# USB.net
KiCad netlist of a schematic drawn in Altium Designer
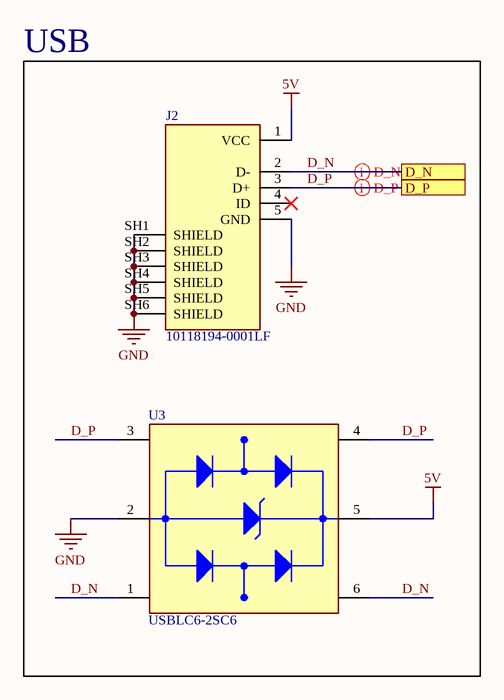
[diagram p0: USB.SchDoc]

(export (version "E")
  (design (tool "Eeschema 10.0.6"))
  (components
    (comp (ref "J2")
      (value "10118194-0001LF")
      (footprint "AMPHENOL_10118194-0001LF")
      (description "Micro USB, Input Output Connectors, B TYPE RECEPTACLE with flange")
      (fields (field (name "MF") "Amphenol ICC"))
      (libsource (lib "PCB_training_Project") (part "10118194-0001LF"))
    )
    (comp (ref "U3")
      (value "USBLC6-2SC6")
      (footprint "SOT95P280X145-6N")
      (description "17V Clamp 5A (8/20Âµs) Ipp Tvs Diode Surface Mount SOT-23-6")
      (fields (field (name "MF") "STMicroelectronics"))
      (libsource (lib "PCB_training_Project") (part "USBLC6-2SC6"))
    )
  )
  (nets
    (net (code "1") (name "/D_N") (class "Default")
      (node (ref "J2") (pin "2") (pinfunction "D-_2") (pintype "passive"))
      (node (ref "U3") (pin "1") (pinfunction "I/O1_IN_1") (pintype "passive"))
      (node (ref "U3") (pin "6") (pinfunction "I/O1_OUT_6") (pintype "passive"))
    )
    (net (code "2") (name "/D_P") (class "Default")
      (node (ref "J2") (pin "3") (pinfunction "D+_3") (pintype "passive"))
      (node (ref "U3") (pin "3") (pinfunction "I/O2_IN_3") (pintype "passive"))
      (node (ref "U3") (pin "4") (pinfunction "I/O2_OUT_4") (pintype "passive"))
    )
    (net (code "3") (name "5V") (class "Default")
      (node (ref "J2") (pin "1") (pinfunction "VCC_1") (pintype "passive"))
      (node (ref "U3") (pin "5") (pinfunction "VBUS_5") (pintype "passive"))
    )
    (net (code "4") (name "GND") (class "Default")
      (node (ref "J2") (pin "5") (pinfunction "GND_5") (pintype "passive"))
      (node (ref "J2") (pin "SH1") (pinfunction "SHIELD_SH1") (pintype "passive"))
      (node (ref "J2") (pin "SH2") (pinfunction "SHIELD_SH2") (pintype "passive"))
      (node (ref "J2") (pin "SH3") (pinfunction "SHIELD_SH3") (pintype "passive"))
      (node (ref "J2") (pin "SH4") (pinfunction "SHIELD_SH4") (pintype "passive"))
      (node (ref "J2") (pin "SH5") (pinfunction "SHIELD_SH5") (pintype "passive"))
      (node (ref "J2") (pin "SH6") (pinfunction "SHIELD_SH6") (pintype "passive"))
      (node (ref "U3") (pin "2") (pinfunction "GND_2") (pintype "passive"))
    )
    (net (code "5") (name "unconnected-(J2-ID-Pad4)") (class "Default")
      (node (ref "J2") (pin "4") (pinfunction "ID_4") (pintype "passive+no_connect"))
    )
  )
)
